# PVDF_pre_amp.net
KiCad netlist of a schematic drawn in EAGLE
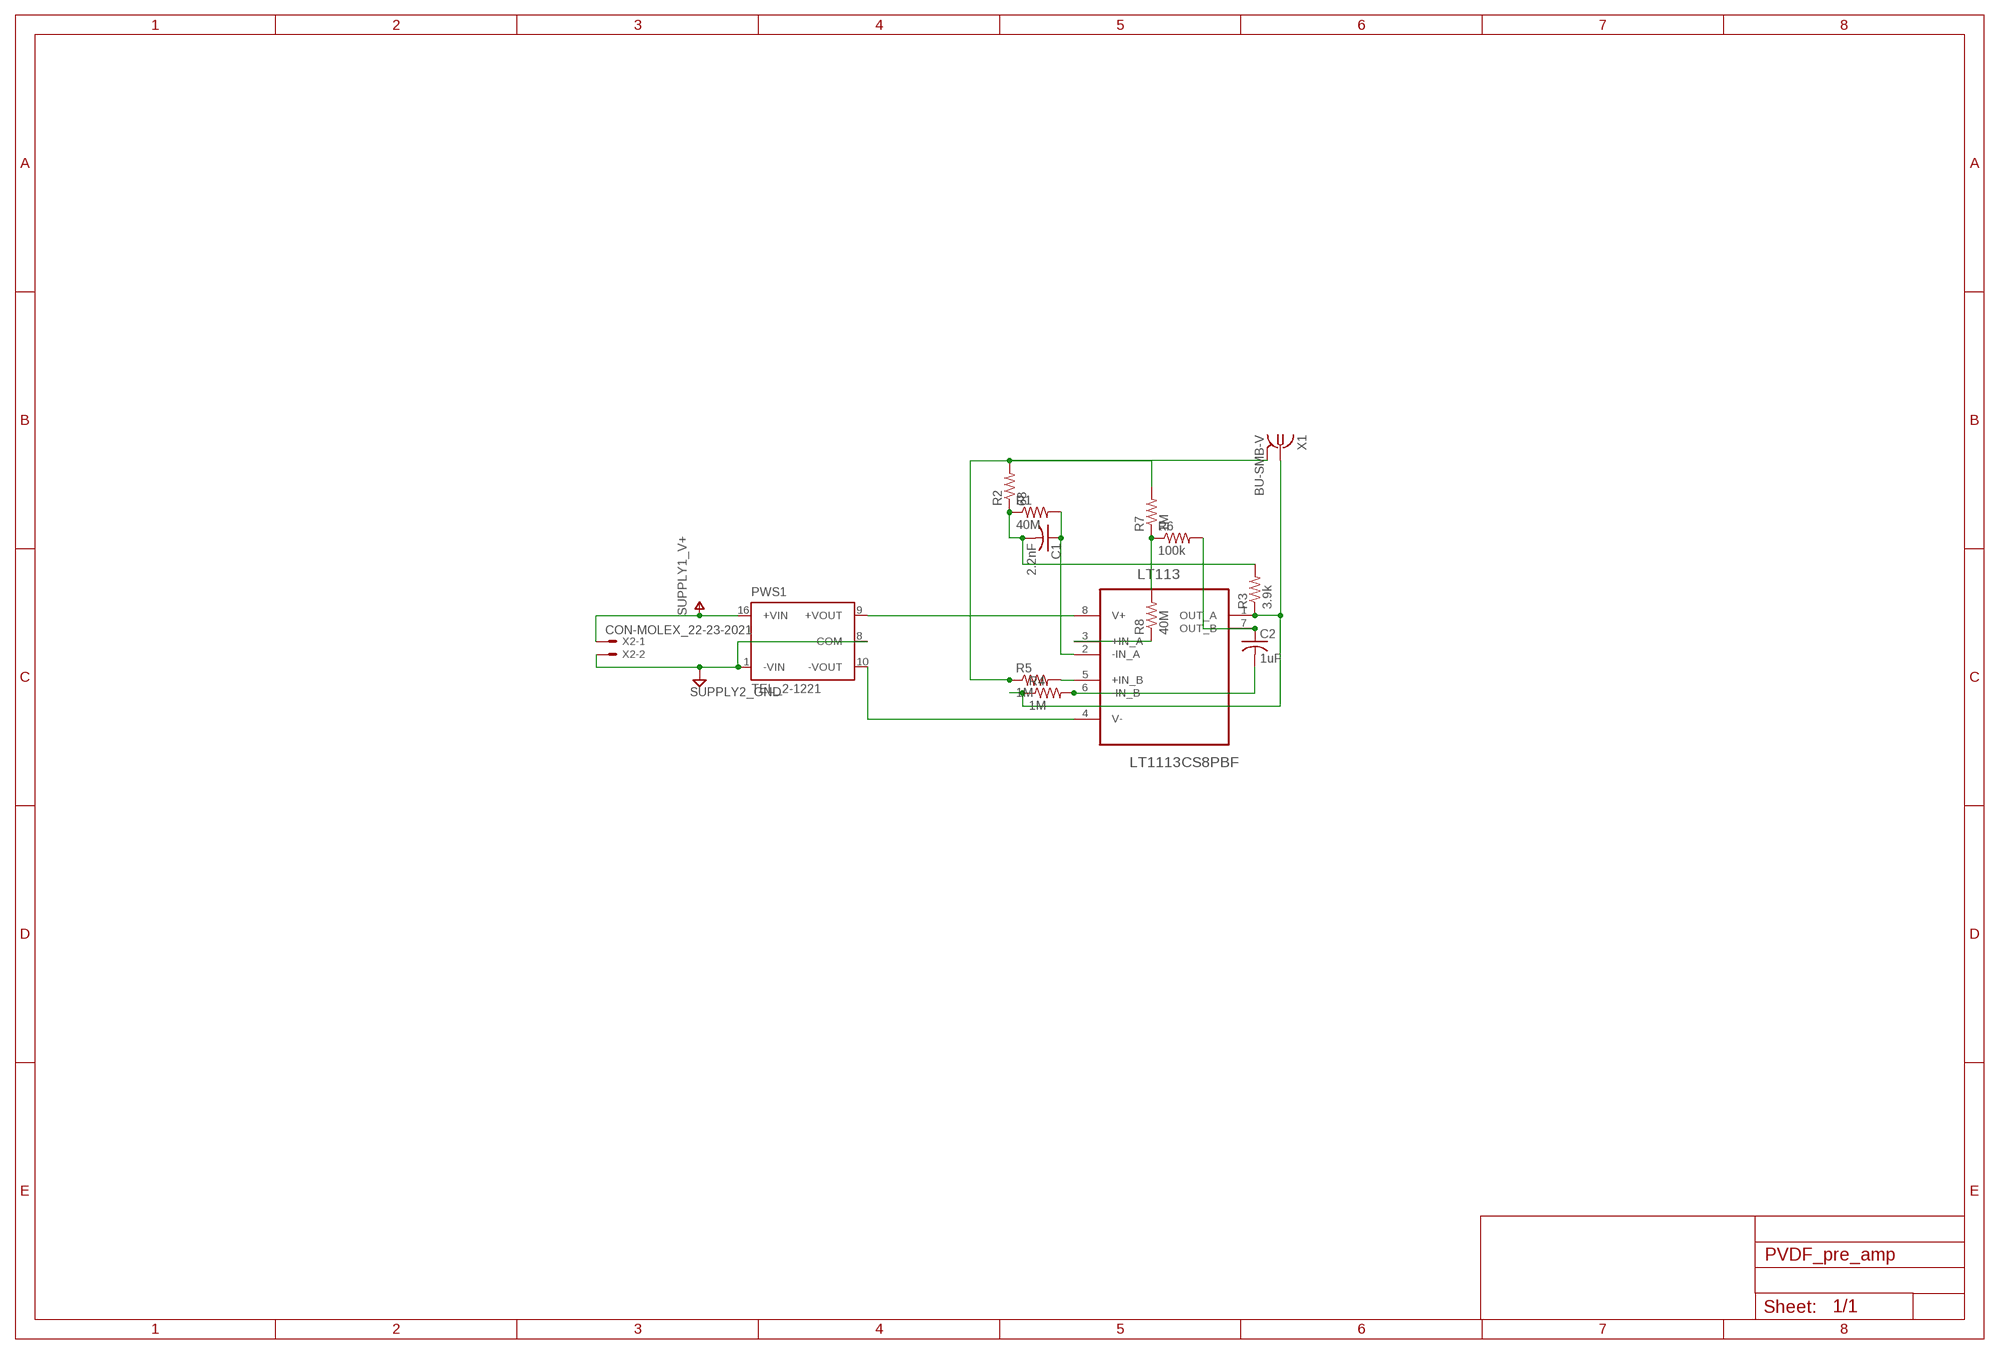
[diagram p0: schematic, sheet 1]

(export (version "E")
  (design (tool "Eeschema 10.0.6"))
  (components
    (comp (ref "C1")
      (value "2.2nF")
      (footprint "eagle-import:ADAFRUIT_C0805K")
      (libsource (lib "eagle-import") (part "ADAFRUIT_C-USC0805K"))
    )
    (comp (ref "C2")
      (value "1uF")
      (footprint "eagle-import:ADAFRUIT_C0805K")
      (libsource (lib "eagle-import") (part "ADAFRUIT_C-USC0805K"))
    )
    (comp (ref "LT113")
      (value "LT1113CS8PBF")
      (footprint "eagle-import:SOIC127P600X175-8N")
      (fields (field (name "MPN") "LT1113CS8#PBF"))
      (libsource (lib "eagle-import") (part "LT1113CS8PBF"))
    )
    (comp (ref "PWS1")
      (value "TEL_2-1221")
      (footprint "eagle-import:TRACOPOWER2W")
      (fields (field (name "MPN") "TEL 2-1221"))
      (libsource (lib "eagle-import") (part "TEL_2-1221"))
    )
    (comp (ref "R1")
      (value "40M")
      (footprint "eagle-import:ADAFRUIT_R0805")
      (libsource (lib "eagle-import") (part "ADAFRUIT_R-US_R0805"))
    )
    (comp (ref "R2")
      (value "68")
      (footprint "eagle-import:ADAFRUIT_R0805")
      (libsource (lib "eagle-import") (part "ADAFRUIT_R-US_R0805"))
    )
    (comp (ref "R3")
      (value "3.9k")
      (footprint "eagle-import:ADAFRUIT_R0805")
      (libsource (lib "eagle-import") (part "ADAFRUIT_R-US_R0805"))
    )
    (comp (ref "R4")
      (value "1M")
      (footprint "eagle-import:ADAFRUIT_R0805")
      (libsource (lib "eagle-import") (part "ADAFRUIT_R-US_R0805"))
    )
    (comp (ref "R5")
      (value "1M")
      (footprint "eagle-import:ADAFRUIT_R0805")
      (libsource (lib "eagle-import") (part "ADAFRUIT_R-US_R0805"))
    )
    (comp (ref "R6")
      (value "100k")
      (footprint "eagle-import:ADAFRUIT_R0805")
      (libsource (lib "eagle-import") (part "ADAFRUIT_R-US_R0805"))
    )
    (comp (ref "R7")
      (value "1M")
      (footprint "eagle-import:ADAFRUIT_R0805")
      (libsource (lib "eagle-import") (part "ADAFRUIT_R-US_R0805"))
    )
    (comp (ref "R8")
      (value "40M")
      (footprint "eagle-import:ADAFRUIT_R0805")
      (libsource (lib "eagle-import") (part "ADAFRUIT_R-US_R0805"))
    )
    (comp (ref "X1")
      (value "BU-SMB-V")
      (footprint "eagle-import:BU-SMB-V")
      (libsource (lib "eagle-import") (part "BU-SMB-V"))
    )
    (comp (ref "X2")
      (value "CON-MOLEX_22-23-2021")
      (footprint "eagle-import:CON-MOLEX_22-23-2021")
      (fields (field (name "MF") "MOLEX") (field (name "MPN") "22-23-2021"))
      (libsource (lib "eagle-import") (part "CON-MOLEX_22-23-2021"))
    )
  )
  (nets
    (net (code "1") (name "Net-(C1-Pad2)") (class "Default")
      (node (ref "C1") (pin "2") (pinfunction "2_2") (pintype "passive"))
      (node (ref "R1") (pin "1") (pinfunction "1_1") (pintype "passive"))
      (node (ref "R2") (pin "1") (pinfunction "1_1") (pintype "passive"))
      (node (ref "R3") (pin "2") (pinfunction "2_2") (pintype "passive"))
    )
    (net (code "2") (name "Net-(LT113-+IN_A)") (class "Default")
      (node (ref "LT113") (pin "3") (pinfunction "+IN_A_3") (pintype "input"))
      (node (ref "R8") (pin "1") (pinfunction "1_1") (pintype "passive"))
    )
    (net (code "3") (name "Net-(LT113-+IN_B)") (class "Default")
      (node (ref "LT113") (pin "5") (pinfunction "+IN_B_5") (pintype "input"))
      (node (ref "R5") (pin "2") (pinfunction "2_2") (pintype "passive"))
    )
    (net (code "4") (name "Net-(LT113--IN_A)") (class "Default")
      (node (ref "C1") (pin "1") (pinfunction "1_1") (pintype "passive"))
      (node (ref "LT113") (pin "2") (pinfunction "-IN_A_2") (pintype "input"))
      (node (ref "R1") (pin "2") (pinfunction "2_2") (pintype "passive"))
    )
    (net (code "5") (name "Net-(LT113--IN_B)") (class "Default")
      (node (ref "C2") (pin "2") (pinfunction "2_2") (pintype "passive"))
      (node (ref "LT113") (pin "6") (pinfunction "-IN_B_6") (pintype "input"))
      (node (ref "R4") (pin "2") (pinfunction "2_2") (pintype "passive"))
    )
    (net (code "6") (name "Net-(LT113-OUT_A)") (class "Default")
      (node (ref "LT113") (pin "1") (pinfunction "OUT_A_1") (pintype "output"))
      (node (ref "R3") (pin "1") (pinfunction "1_1") (pintype "passive"))
      (node (ref "R4") (pin "1") (pinfunction "1_1") (pintype "passive"))
      (node (ref "X1") (pin "1") (pinfunction "1_1") (pintype "passive"))
    )
    (net (code "7") (name "Net-(LT113-OUT_B)") (class "Default")
      (node (ref "C2") (pin "1") (pinfunction "1_1") (pintype "passive"))
      (node (ref "LT113") (pin "7") (pinfunction "OUT_B_7") (pintype "output"))
      (node (ref "R6") (pin "2") (pinfunction "2_2") (pintype "passive"))
    )
    (net (code "8") (name "Net-(LT113-V+)") (class "Default")
      (node (ref "LT113") (pin "8") (pinfunction "V+_8") (pintype "power_in"))
      (node (ref "PWS1") (pin "9") (pinfunction "+VOUT_9") (pintype "passive"))
    )
    (net (code "9") (name "Net-(LT113-V-)") (class "Default")
      (node (ref "LT113") (pin "4") (pinfunction "V-_4") (pintype "power_in"))
      (node (ref "PWS1") (pin "10") (pinfunction "-VOUT_10") (pintype "passive"))
    )
    (net (code "10") (name "Net-(R6-Pad1)") (class "Default")
      (node (ref "R6") (pin "1") (pinfunction "1_1") (pintype "passive"))
      (node (ref "R7") (pin "1") (pinfunction "1_1") (pintype "passive"))
      (node (ref "R8") (pin "2") (pinfunction "2_2") (pintype "passive"))
    )
    (net (code "11") (name "SUPPLY1_V+") (class "Default")
      (node (ref "PWS1") (pin "16") (pinfunction "+VIN_16") (pintype "input"))
      (node (ref "X2") (pin "1") (pinfunction "S_1") (pintype "passive"))
    )
    (net (code "12") (name "SUPPLY2_GND") (class "Default")
      (node (ref "PWS1") (pin "1") (pinfunction "-VIN_1") (pintype "input"))
      (node (ref "PWS1") (pin "8") (pinfunction "COM_8") (pintype "passive"))
      (node (ref "R2") (pin "2") (pinfunction "2_2") (pintype "passive"))
      (node (ref "R5") (pin "1") (pinfunction "1_1") (pintype "passive"))
      (node (ref "R7") (pin "2") (pinfunction "2_2") (pintype "passive"))
      (node (ref "X1") (pin "2") (pinfunction "2_2") (pintype "passive"))
      (node (ref "X1") (pin "3") (pinfunction "2_3") (pintype "passive"))
      (node (ref "X1") (pin "4") (pinfunction "2_4") (pintype "passive"))
      (node (ref "X1") (pin "5") (pinfunction "2_5") (pintype "passive"))
      (node (ref "X2") (pin "2") (pinfunction "S_2") (pintype "passive"))
    )
  )
)
